# SD.net
KiCad netlist of a schematic drawn in Altium Designer
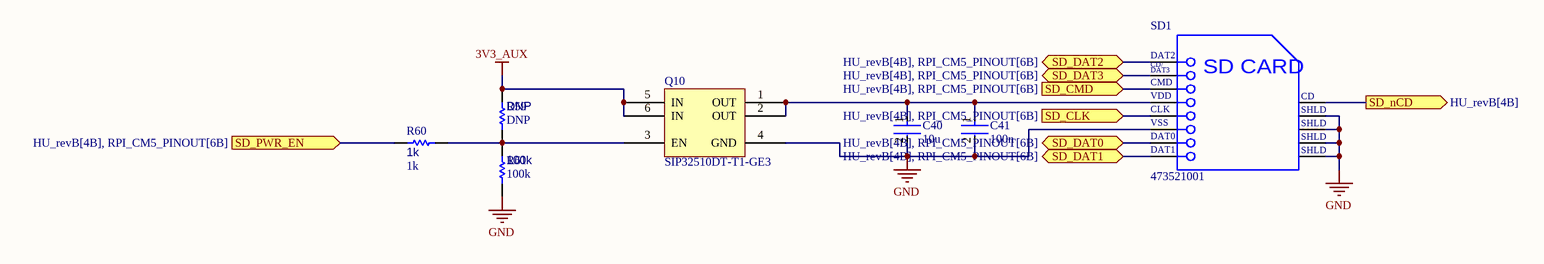
[diagram p0: SD.SchDoc]

(export (version "E")
  (design (tool "Eeschema 10.0.6"))
  (components
    (comp (ref "C40")
      (value "10u")
      (footprint "FP-0402-L_1_0_0_05-W_0_5-IPC_A")
      (description "LARGE PADS, 0402 CAP, CHANGE COMMENT TO MATCH REAL P/N")
      (libsource (lib "Space Concordia") (part "b4654b650e69147ec39a6b967a45e02"))
    )
    (comp (ref "C41")
      (value "100n")
      (footprint "FP-0402-L_1_0_0_05-W_0_5-IPC_A")
      (description "LARGE PADS, 0402 CAP, CHANGE COMMENT TO MATCH REAL P/N")
      (libsource (lib "Space Concordia") (part "b4654b650e69147ec39a6b967a45e02"))
    )
    (comp (ref "Q10")
      (value "SIP32510DT-T1-GE3")
      (footprint "SOT95P284X110-6N")
      (description "Power Switch ICs – Power Distribution; VISHAY; SIP32510DT-T1-GE3; 1; 1; 5.5 V; SOT-23-6")
      (libsource (lib "Space Concordia") (part "SIP32510DT-T1-GE3"))
    )
    (comp (ref "R59")
      (value "DNP")
      (footprint "R0603B")
      (description "Resistor")
      (fields (field (name "ALTIUM_VALUE") "DNP"))
      (libsource (lib "Space Concordia") (part "Resistor"))
    )
    (comp (ref "R60")
      (value "1k")
      (footprint "R0603B")
      (description "Resistor")
      (fields (field (name "ALTIUM_VALUE") "1k"))
      (libsource (lib "Space Concordia") (part "Resistor"))
    )
    (comp (ref "R61")
      (value "100k")
      (footprint "R0603B")
      (description "Resistor")
      (fields (field (name "ALTIUM_VALUE") "100k"))
      (libsource (lib "Space Concordia") (part "Resistor"))
    )
    (comp (ref "SD1")
      (value "473521001")
      (footprint "MOLX-473521001_V")
      (description "MicroSD(TM), Pitch 1.1 mm, 8 Position, Height 1.88 mm, -20 to 85 degC, RoHS, Tape and Reel")
      (fields (field (name "MANUFACTURER") "Molex"))
      (libsource (lib "Altium Content Vault") (part "CN-SD-8-1SW-4S"))
    )
  )
  (nets
    (net (code "1") (name "/SD_CLK") (class "Default")
      (node (ref "SD1") (pin "5") (pinfunction "CLK_5") (pintype "passive"))
    )
    (net (code "2") (name "/SD_CMD") (class "Default")
      (node (ref "SD1") (pin "3") (pinfunction "CMD_3") (pintype "passive"))
    )
    (net (code "3") (name "/SD_DAT0") (class "Default")
      (node (ref "SD1") (pin "7") (pinfunction "DAT0_7") (pintype "passive"))
    )
    (net (code "4") (name "/SD_DAT1") (class "Default")
      (node (ref "SD1") (pin "8") (pinfunction "DAT1_8") (pintype "passive"))
    )
    (net (code "5") (name "/SD_DAT2") (class "Default")
      (node (ref "SD1") (pin "1") (pinfunction "DAT2_1") (pintype "passive"))
    )
    (net (code "6") (name "/SD_DAT3") (class "Default")
      (node (ref "SD1") (pin "2") (pinfunction "CD/DAT3_2") (pintype "passive"))
    )
    (net (code "7") (name "/SD_PWR_EN") (class "Default")
      (node (ref "R60") (pin "2") (pinfunction "2_2") (pintype "passive"))
    )
    (net (code "8") (name "/SD_nCD") (class "Default")
      (node (ref "SD1") (pin "9") (pinfunction "CD_9") (pintype "passive"))
    )
    (net (code "9") (name "3V3_AUX") (class "Default")
      (node (ref "Q10") (pin "5") (pinfunction "IN_5") (pintype "passive"))
      (node (ref "Q10") (pin "6") (pinfunction "IN_6") (pintype "passive"))
      (node (ref "R59") (pin "2") (pinfunction "2_2") (pintype "passive"))
    )
    (net (code "10") (name "GND") (class "Default")
      (node (ref "C40") (pin "2") (pinfunction "2_2") (pintype "passive"))
      (node (ref "C41") (pin "2") (pinfunction "2_2") (pintype "passive"))
      (node (ref "Q10") (pin "4") (pinfunction "GND_4") (pintype "passive"))
      (node (ref "R61") (pin "1") (pinfunction "1_1") (pintype "passive"))
      (node (ref "SD1") (pin "10") (pinfunction "SHLD_10") (pintype "passive"))
      (node (ref "SD1") (pin "11") (pinfunction "SHLD_11") (pintype "passive"))
      (node (ref "SD1") (pin "12") (pinfunction "SHLD_12") (pintype "passive"))
      (node (ref "SD1") (pin "13") (pinfunction "SHLD_13") (pintype "passive"))
      (node (ref "SD1") (pin "6") (pinfunction "VSS_6") (pintype "passive"))
    )
    (net (code "11") (name "Net-(Q10-EN)") (class "Default")
      (node (ref "Q10") (pin "3") (pinfunction "EN_3") (pintype "passive"))
      (node (ref "R59") (pin "1") (pinfunction "1_1") (pintype "passive"))
      (node (ref "R60") (pin "1") (pinfunction "1_1") (pintype "passive"))
      (node (ref "R61") (pin "2") (pinfunction "2_2") (pintype "passive"))
    )
    (net (code "12") (name "Net-(SD1-VDD)") (class "Default")
      (node (ref "C40") (pin "1") (pinfunction "1_1") (pintype "passive"))
      (node (ref "C41") (pin "1") (pinfunction "1_1") (pintype "passive"))
      (node (ref "Q10") (pin "1") (pinfunction "OUT_1") (pintype "passive"))
      (node (ref "Q10") (pin "2") (pinfunction "OUT_2") (pintype "passive"))
      (node (ref "SD1") (pin "4") (pinfunction "VDD_4") (pintype "passive"))
    )
  )
)
